# Interactive_SparkFun_Badge.net
KiCad netlist of a schematic drawn in EAGLE
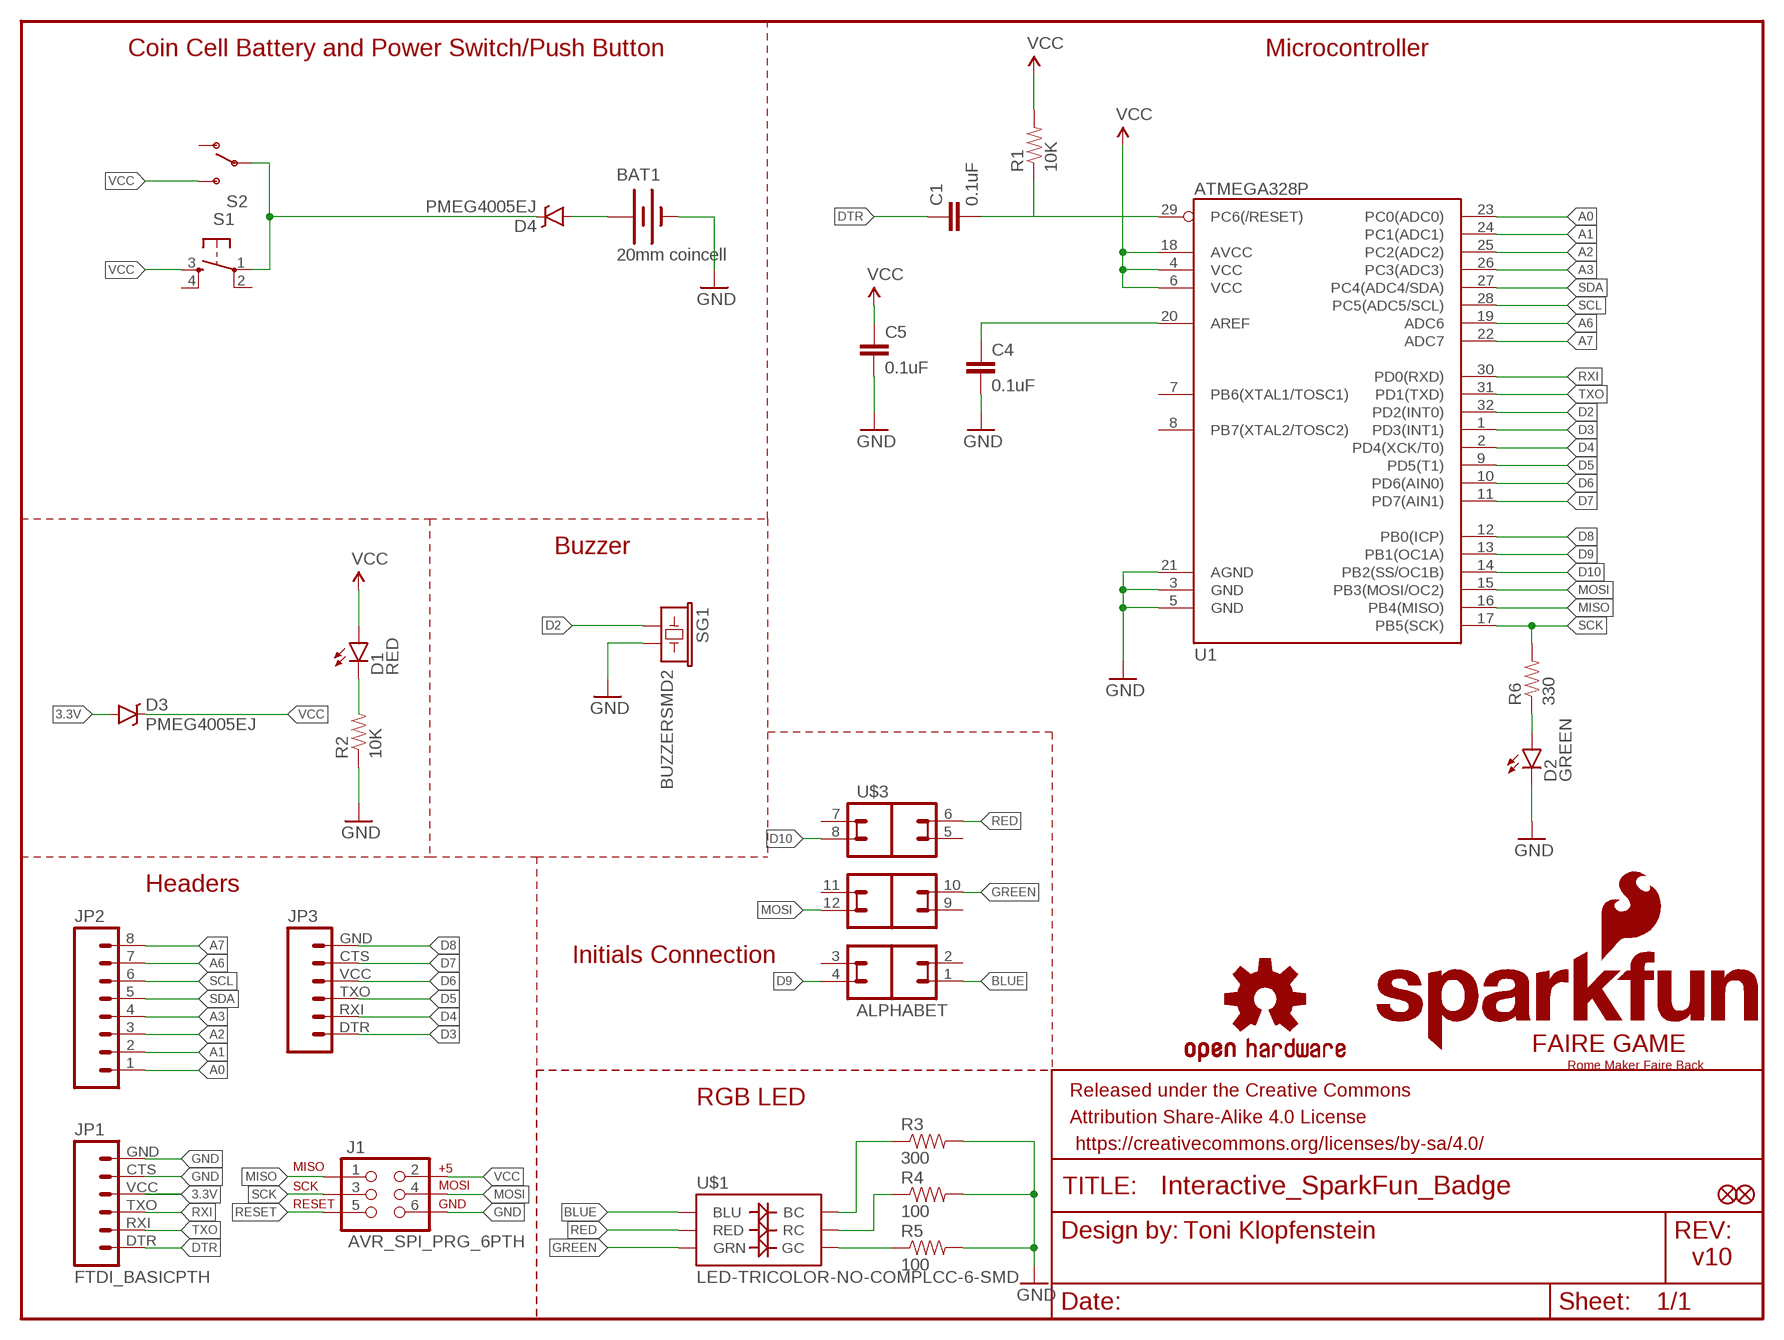
[diagram p0: schematic, sheet 1]

(export (version "E")
  (design (tool "Eeschema 10.0.6"))
  (components
    (comp (ref "BAT1")
      (value "20mm coincell")
      (footprint "eagle-import:BATTCON_20MM_4LEGS")
      (libsource (lib "eagle-import") (part "BATTERY20MM_4LEGS"))
    )
    (comp (ref "C1")
      (value "0.1uF")
      (footprint "eagle-import:0603-CAP")
      (libsource (lib "eagle-import") (part "0.1UF-25V(+80/-20%)(0603)"))
    )
    (comp (ref "C4")
      (value "0.1uF")
      (footprint "eagle-import:0603-CAP")
      (libsource (lib "eagle-import") (part "0.1UF-25V(+80/-20%)(0603)"))
    )
    (comp (ref "C5")
      (value "0.1uF")
      (footprint "eagle-import:0603-CAP")
      (libsource (lib "eagle-import") (part "0.1UF-25V(+80/-20%)(0603)"))
    )
    (comp (ref "D1")
      (value "RED")
      (footprint "eagle-import:LED-0603")
      (libsource (lib "eagle-import") (part "LED-RED0603"))
    )
    (comp (ref "D2")
      (value "GREEN")
      (footprint "eagle-import:LED-0603")
      (libsource (lib "eagle-import") (part "LED-GREEN0603"))
    )
    (comp (ref "D3")
      (value "PMEG4005EJ")
      (footprint "eagle-import:SOD-323")
      (libsource (lib "eagle-import") (part "DIODE-SCHOTTKY-PMEG4005EJ"))
    )
    (comp (ref "D4")
      (value "PMEG4005EJ")
      (footprint "eagle-import:SOD-323")
      (libsource (lib "eagle-import") (part "DIODE-SCHOTTKY-PMEG4005EJ"))
    )
    (comp (ref "FID1")
      (value "FIDUCIAL1X2")
      (footprint "eagle-import:FIDUCIAL-1X2")
      (libsource (lib "eagle-import") (part "FIDUCIAL1X2"))
    )
    (comp (ref "FID2")
      (value "FIDUCIAL1X2")
      (footprint "eagle-import:FIDUCIAL-1X2")
      (libsource (lib "eagle-import") (part "FIDUCIAL1X2"))
    )
    (comp (ref "FRAME1")
      (value "FRAME-LETTER")
      (footprint "eagle-import:CREATIVE_COMMONS")
      (libsource (lib "eagle-import") (part "FRAME-LETTER"))
    )
    (comp (ref "J1")
      (value "AVR_SPI_PRG_6PTH")
      (footprint "eagle-import:2X3")
      (libsource (lib "eagle-import") (part "AVR_SPI_PRG_6PTH"))
    )
    (comp (ref "JP1")
      (value "FTDI_BASICPTH")
      (footprint "eagle-import:FTDI_BASIC")
      (libsource (lib "eagle-import") (part "FTDI_BASICPTH"))
    )
    (comp (ref "JP2")
      (value "M081X08")
      (footprint "eagle-import:1X08")
      (libsource (lib "eagle-import") (part "M081X08"))
    )
    (comp (ref "JP3")
      (value "M06SIP")
      (footprint "eagle-import:1X06")
      (libsource (lib "eagle-import") (part "M06SIP"))
    )
    (comp (ref "LOGO1")
      (value "OSHW-LOGOM")
      (footprint "eagle-import:OSHW-LOGO-M")
      (libsource (lib "eagle-import") (part "OSHW-LOGOM"))
    )
    (comp (ref "R1")
      (value "10K")
      (footprint "eagle-import:0603-RES")
      (libsource (lib "eagle-import") (part "10KOHM1/10W1%(0603)0603"))
    )
    (comp (ref "R2")
      (value "10K")
      (footprint "eagle-import:0603-RES")
      (libsource (lib "eagle-import") (part "10KOHM1/10W1%(0603)0603"))
    )
    (comp (ref "R3")
      (value "300")
      (footprint "eagle-import:0603-RES")
      (libsource (lib "eagle-import") (part "300OHM-1/10W-1%(0603)"))
    )
    (comp (ref "R4")
      (value "100")
      (footprint "eagle-import:0603-RES")
      (libsource (lib "eagle-import") (part "100OHM1/10W1%(0603)"))
    )
    (comp (ref "R5")
      (value "100")
      (footprint "eagle-import:0603-RES")
      (libsource (lib "eagle-import") (part "100OHM1/10W1%(0603)"))
    )
    (comp (ref "R6")
      (value "330")
      (footprint "eagle-import:0603-RES")
      (libsource (lib "eagle-import") (part "330OHM1/10W1%(0603)"))
    )
    (comp (ref "S1")
      (value "TAC_SWITCHSMD")
      (footprint "eagle-import:TACTILE-SWITCH-SMD")
      (libsource (lib "eagle-import") (part "TAC_SWITCHSMD"))
    )
    (comp (ref "S2")
      (value "SWITCH-SPDTSMD")
      (footprint "eagle-import:AYZ0202")
      (libsource (lib "eagle-import") (part "SWITCH-SPDTSMD"))
    )
    (comp (ref "SG1")
      (value "BUZZERSMD2")
      (footprint "eagle-import:BUZZER-CCV")
      (libsource (lib "eagle-import") (part "BUZZERSMD2"))
    )
    (comp (ref "U$1")
      (value "LED-TRICOLOR-NO-COMPLCC-6-SMD")
      (footprint "eagle-import:PLCC-6-LED")
      (libsource (lib "eagle-import") (part "LED-TRICOLOR-NO-COMPLCC-6-SMD"))
    )
    (comp (ref "U$2")
      (value "ROME_FAIRE_BACK")
      (footprint "eagle-import:ROME_BACK")
      (libsource (lib "eagle-import") (part "ROME_FAIRE_BACK"))
    )
    (comp (ref "U$3")
      (value "ALPHABET")
      (footprint "eagle-import:INITIALS")
      (libsource (lib "eagle-import") (part "ALPHABET"))
    )
    (comp (ref "U$4")
      (value "FAIRE_GAME_SILK")
      (footprint "eagle-import:FAIRE_GAME_SILK")
      (libsource (lib "eagle-import") (part "FAIRE_GAME_SILK"))
    )
    (comp (ref "U1")
      (value "ATMEGA328P")
      (footprint "eagle-import:TQFP32-08")
      (libsource (lib "eagle-import") (part "ATMEGA328_SMT"))
    )
  )
  (nets
    (net (code "1") (name "3.3V") (class "Default")
      (node (ref "D3") (pin "A") (pinfunction "A_A") (pintype "passive"))
      (node (ref "JP1") (pin "VCC") (pinfunction "4_VCC") (pintype "passive"))
    )
    (net (code "2") (name "A0") (class "Default")
      (node (ref "JP2") (pin "1") (pinfunction "1_1") (pintype "passive"))
      (node (ref "U1") (pin "23") (pinfunction "PC0(ADC0)_23") (pintype "bidirectional"))
    )
    (net (code "3") (name "A1") (class "Default")
      (node (ref "JP2") (pin "2") (pinfunction "2_2") (pintype "passive"))
      (node (ref "U1") (pin "24") (pinfunction "PC1(ADC1)_24") (pintype "bidirectional"))
    )
    (net (code "4") (name "A2") (class "Default")
      (node (ref "JP2") (pin "3") (pinfunction "3_3") (pintype "passive"))
      (node (ref "U1") (pin "25") (pinfunction "PC2(ADC2)_25") (pintype "bidirectional"))
    )
    (net (code "5") (name "A3") (class "Default")
      (node (ref "JP2") (pin "4") (pinfunction "4_4") (pintype "passive"))
      (node (ref "U1") (pin "26") (pinfunction "PC3(ADC3)_26") (pintype "bidirectional"))
    )
    (net (code "6") (name "A6") (class "Default")
      (node (ref "JP2") (pin "7") (pinfunction "7_7") (pintype "passive"))
      (node (ref "U1") (pin "19") (pinfunction "ADC6_19") (pintype "bidirectional"))
    )
    (net (code "7") (name "A7") (class "Default")
      (node (ref "JP2") (pin "8") (pinfunction "8_8") (pintype "passive"))
      (node (ref "U1") (pin "22") (pinfunction "ADC7_22") (pintype "bidirectional"))
    )
    (net (code "8") (name "BLUE") (class "Default")
      (node (ref "U$1") (pin "AB") (pinfunction "BLU_AB") (pintype "bidirectional"))
      (node (ref "U$3") (pin "1") (pinfunction "1_1") (pintype "passive"))
    )
    (net (code "9") (name "D2") (class "Default")
      (node (ref "SG1") (pin "+") (pinfunction "1_+") (pintype "passive"))
      (node (ref "U1") (pin "32") (pinfunction "PD2(INT0)_32") (pintype "bidirectional"))
    )
    (net (code "10") (name "D3") (class "Default")
      (node (ref "JP3") (pin "DTR") (pinfunction "1_DTR") (pintype "passive"))
      (node (ref "U1") (pin "1") (pinfunction "PD3(INT1)_1") (pintype "bidirectional"))
    )
    (net (code "11") (name "D4") (class "Default")
      (node (ref "JP3") (pin "RXI") (pinfunction "2_RXI") (pintype "passive"))
      (node (ref "U1") (pin "2") (pinfunction "PD4(XCK/T0)_2") (pintype "bidirectional"))
    )
    (net (code "12") (name "D5") (class "Default")
      (node (ref "JP3") (pin "TXO") (pinfunction "3_TXO") (pintype "passive"))
      (node (ref "U1") (pin "9") (pinfunction "PD5(T1)_9") (pintype "bidirectional"))
    )
    (net (code "13") (name "D6") (class "Default")
      (node (ref "JP3") (pin "VCC") (pinfunction "4_VCC") (pintype "passive"))
      (node (ref "U1") (pin "10") (pinfunction "PD6(AIN0)_10") (pintype "bidirectional"))
    )
    (net (code "14") (name "D7") (class "Default")
      (node (ref "JP3") (pin "CTS") (pinfunction "5_CTS") (pintype "passive"))
      (node (ref "U1") (pin "11") (pinfunction "PD7(AIN1)_11") (pintype "bidirectional"))
    )
    (net (code "15") (name "D8") (class "Default")
      (node (ref "JP3") (pin "GND") (pinfunction "6_GND") (pintype "passive"))
      (node (ref "U1") (pin "12") (pinfunction "PB0(ICP)_12") (pintype "bidirectional"))
    )
    (net (code "16") (name "D9") (class "Default")
      (node (ref "U$3") (pin "4") (pinfunction "4_4") (pintype "passive"))
      (node (ref "U1") (pin "13") (pinfunction "PB1(OC1A)_13") (pintype "bidirectional"))
    )
    (net (code "17") (name "D10") (class "Default")
      (node (ref "U$3") (pin "8") (pinfunction "8_8") (pintype "passive"))
      (node (ref "U1") (pin "14") (pinfunction "PB2(SS/OC1B)_14") (pintype "bidirectional"))
    )
    (net (code "18") (name "DTR") (class "Default")
      (node (ref "C1") (pin "1") (pinfunction "1_1") (pintype "passive"))
      (node (ref "JP1") (pin "DTR") (pinfunction "1_DTR") (pintype "passive"))
    )
    (net (code "19") (name "GND") (class "Default")
      (node (ref "BAT1") (pin "2") (pinfunction "-_2") (pintype "power_in"))
      (node (ref "C4") (pin "2") (pinfunction "2_2") (pintype "passive"))
      (node (ref "C5") (pin "2") (pinfunction "2_2") (pintype "passive"))
      (node (ref "D2") (pin "C") (pinfunction "C_C") (pintype "passive"))
      (node (ref "J1") (pin "6") (pinfunction "6_6") (pintype "passive"))
      (node (ref "JP1") (pin "CTS") (pinfunction "5_CTS") (pintype "passive"))
      (node (ref "JP1") (pin "GND") (pinfunction "6_GND") (pintype "passive"))
      (node (ref "R2") (pin "1") (pinfunction "1_1") (pintype "passive"))
      (node (ref "R3") (pin "2") (pinfunction "2_2") (pintype "passive"))
      (node (ref "R4") (pin "2") (pinfunction "2_2") (pintype "passive"))
      (node (ref "R5") (pin "2") (pinfunction "2_2") (pintype "passive"))
      (node (ref "SG1") (pin "-") (pinfunction "2_-") (pintype "passive"))
      (node (ref "U1") (pin "21") (pinfunction "AGND_21") (pintype "bidirectional"))
      (node (ref "U1") (pin "3") (pinfunction "GND_3") (pintype "bidirectional"))
      (node (ref "U1") (pin "5") (pinfunction "GND_5") (pintype "bidirectional"))
    )
    (net (code "20") (name "GREEN") (class "Default")
      (node (ref "U$1") (pin "AG") (pinfunction "GRN_AG") (pintype "bidirectional"))
      (node (ref "U$3") (pin "10") (pinfunction "10_10") (pintype "passive"))
    )
    (net (code "21") (name "MISO") (class "Default")
      (node (ref "J1") (pin "1") (pinfunction "1_1") (pintype "passive"))
      (node (ref "U1") (pin "16") (pinfunction "PB4(MISO)_16") (pintype "bidirectional"))
    )
    (net (code "22") (name "MOSI") (class "Default")
      (node (ref "J1") (pin "4") (pinfunction "4_4") (pintype "passive"))
      (node (ref "U$3") (pin "12") (pinfunction "12_12") (pintype "passive"))
      (node (ref "U1") (pin "15") (pinfunction "PB3(MOSI/OC2)_15") (pintype "bidirectional"))
    )
    (net (code "23") (name "Net-(BAT1-+)") (class "Default")
      (node (ref "BAT1") (pin "1") (pinfunction "+_1") (pintype "power_in"))
      (node (ref "D4") (pin "A") (pinfunction "A_A") (pintype "passive"))
    )
    (net (code "24") (name "Net-(D1-PadC)") (class "Default")
      (node (ref "D1") (pin "C") (pinfunction "C_C") (pintype "passive"))
      (node (ref "R2") (pin "2") (pinfunction "2_2") (pintype "passive"))
    )
    (net (code "25") (name "Net-(D2-PadA)") (class "Default")
      (node (ref "D2") (pin "A") (pinfunction "A_A") (pintype "passive"))
      (node (ref "R6") (pin "1") (pinfunction "1_1") (pintype "passive"))
    )
    (net (code "26") (name "Net-(S2-P)") (class "Default")
      (node (ref "D4") (pin "C") (pinfunction "C_C") (pintype "passive"))
      (node (ref "S1") (pin "1") (pinfunction "1_1") (pintype "passive"))
      (node (ref "S2") (pin "2") (pinfunction "P_2") (pintype "passive"))
    )
    (net (code "27") (name "Net-(U$1-BC)") (class "Default")
      (node (ref "R3") (pin "1") (pinfunction "1_1") (pintype "passive"))
      (node (ref "U$1") (pin "CB") (pinfunction "BC_CB") (pintype "bidirectional"))
    )
    (net (code "28") (name "Net-(U$1-GC)") (class "Default")
      (node (ref "R5") (pin "1") (pinfunction "1_1") (pintype "passive"))
      (node (ref "U$1") (pin "CG") (pinfunction "GC_CG") (pintype "bidirectional"))
    )
    (net (code "29") (name "Net-(U$1-RC)") (class "Default")
      (node (ref "R4") (pin "1") (pinfunction "1_1") (pintype "passive"))
      (node (ref "U$1") (pin "CR") (pinfunction "RC_CR") (pintype "bidirectional"))
    )
    (net (code "30") (name "Net-(U1-AREF)") (class "Default")
      (node (ref "C4") (pin "1") (pinfunction "1_1") (pintype "passive"))
      (node (ref "U1") (pin "20") (pinfunction "AREF_20") (pintype "bidirectional"))
    )
    (net (code "31") (name "RED") (class "Default")
      (node (ref "U$1") (pin "AR") (pinfunction "RED_AR") (pintype "bidirectional"))
      (node (ref "U$3") (pin "6") (pinfunction "6_6") (pintype "passive"))
    )
    (net (code "32") (name "RESET") (class "Default")
      (node (ref "C1") (pin "2") (pinfunction "2_2") (pintype "passive"))
      (node (ref "J1") (pin "5") (pinfunction "5_5") (pintype "passive"))
      (node (ref "R1") (pin "1") (pinfunction "1_1") (pintype "passive"))
      (node (ref "U1") (pin "29") (pinfunction "PC6(/RESET)_29") (pintype "bidirectional"))
    )
    (net (code "33") (name "RXI") (class "Default")
      (node (ref "JP1") (pin "TXO") (pinfunction "3_TXO") (pintype "passive"))
      (node (ref "U1") (pin "30") (pinfunction "PD0(RXD)_30") (pintype "bidirectional"))
    )
    (net (code "34") (name "SCK") (class "Default")
      (node (ref "J1") (pin "3") (pinfunction "3_3") (pintype "passive"))
      (node (ref "R6") (pin "2") (pinfunction "2_2") (pintype "passive"))
      (node (ref "U1") (pin "17") (pinfunction "PB5(SCK)_17") (pintype "bidirectional"))
    )
    (net (code "35") (name "SCL") (class "Default")
      (node (ref "JP2") (pin "6") (pinfunction "6_6") (pintype "passive"))
      (node (ref "U1") (pin "28") (pinfunction "PC5(ADC5/SCL)_28") (pintype "bidirectional"))
    )
    (net (code "36") (name "SDA") (class "Default")
      (node (ref "JP2") (pin "5") (pinfunction "5_5") (pintype "passive"))
      (node (ref "U1") (pin "27") (pinfunction "PC4(ADC4/SDA)_27") (pintype "bidirectional"))
    )
    (net (code "37") (name "TXO") (class "Default")
      (node (ref "JP1") (pin "RXI") (pinfunction "2_RXI") (pintype "passive"))
      (node (ref "U1") (pin "31") (pinfunction "PD1(TXD)_31") (pintype "bidirectional"))
    )
    (net (code "38") (name "VCC") (class "Default")
      (node (ref "C5") (pin "1") (pinfunction "1_1") (pintype "passive"))
      (node (ref "D1") (pin "A") (pinfunction "A_A") (pintype "passive"))
      (node (ref "D3") (pin "C") (pinfunction "C_C") (pintype "passive"))
      (node (ref "J1") (pin "2") (pinfunction "2_2") (pintype "passive"))
      (node (ref "R1") (pin "2") (pinfunction "2_2") (pintype "passive"))
      (node (ref "S1") (pin "3") (pinfunction "3_3") (pintype "passive"))
      (node (ref "S2") (pin "3") (pinfunction "S_3") (pintype "passive"))
      (node (ref "U1") (pin "18") (pinfunction "AVCC_18") (pintype "bidirectional"))
      (node (ref "U1") (pin "4") (pinfunction "VCC_4") (pintype "bidirectional"))
      (node (ref "U1") (pin "6") (pinfunction "VCC_6") (pintype "bidirectional"))
    )
    (net (code "39") (name "unconnected-(S1-Pad2)") (class "Default")
      (node (ref "S1") (pin "2") (pinfunction "2_2") (pintype "passive"))
    )
    (net (code "40") (name "unconnected-(S1-Pad4)") (class "Default")
      (node (ref "S1") (pin "4") (pinfunction "4_4") (pintype "passive"))
    )
    (net (code "41") (name "unconnected-(S2-O-Pad1)") (class "Default")
      (node (ref "S2") (pin "1") (pinfunction "O_1") (pintype "passive"))
    )
    (net (code "42") (name "unconnected-(U$3-Pad2)") (class "Default")
      (node (ref "U$3") (pin "2") (pinfunction "2_2") (pintype "passive"))
    )
    (net (code "43") (name "unconnected-(U$3-Pad3)") (class "Default")
      (node (ref "U$3") (pin "3") (pinfunction "3_3") (pintype "passive"))
    )
    (net (code "44") (name "unconnected-(U$3-Pad5)") (class "Default")
      (node (ref "U$3") (pin "5") (pinfunction "5_5") (pintype "passive"))
    )
    (net (code "45") (name "unconnected-(U$3-Pad7)") (class "Default")
      (node (ref "U$3") (pin "7") (pinfunction "7_7") (pintype "passive"))
    )
    (net (code "46") (name "unconnected-(U$3-Pad9)") (class "Default")
      (node (ref "U$3") (pin "9") (pinfunction "9_9") (pintype "passive"))
    )
    (net (code "47") (name "unconnected-(U$3-Pad11)") (class "Default")
      (node (ref "U$3") (pin "11") (pinfunction "11_11") (pintype "passive"))
    )
    (net (code "48") (name "unconnected-(U1-PB6(XTAL1{slash}TOSC1)-Pad7)") (class "Default")
      (node (ref "U1") (pin "7") (pinfunction "PB6(XTAL1/TOSC1)_7") (pintype "bidirectional"))
    )
    (net (code "49") (name "unconnected-(U1-PB7(XTAL2{slash}TOSC2)-Pad8)") (class "Default")
      (node (ref "U1") (pin "8") (pinfunction "PB7(XTAL2/TOSC2)_8") (pintype "bidirectional"))
    )
  )
)
